# Sheet1.net
KiCad netlist of a schematic drawn in Altium Designer
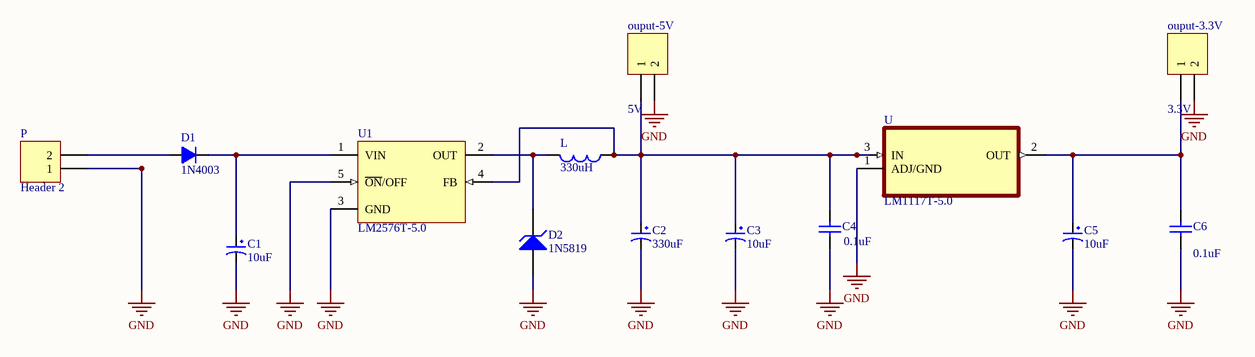
[diagram p0: Sheet1.SchDoc]

(export (version "E")
  (design (tool "Eeschema 10.0.6"))
  (components
    (comp (ref "C1")
      (value "10uF")
      (footprint "CP1/2")
      (description "Cap P  0,1uF < 22uF , 16 - 50V")
      (libsource (lib "syhaunguyen") (part "CP1"))
    )
    (comp (ref "C2")
      (value "330uF")
      (footprint "CP1.5/3.4")
      (description "Cap 100uF/35V - 470uF/16V")
      (libsource (lib "syhaunguyen") (part "CP3"))
    )
    (comp (ref "C3")
      (value "10uF")
      (footprint "CP1/2")
      (description "Cap P  0,1uF < 22uF , 16 - 50V")
      (libsource (lib "syhaunguyen") (part "CP1"))
    )
    (comp (ref "C4")
      (value "0.1uF")
      (footprint "C3MM")
      (description "Capacitor")
      (fields (field (name "PUBLISHER") "Altium Limited"))
      (libsource (lib "Schematic") (part "Cap"))
    )
    (comp (ref "C5")
      (value "10uF")
      (footprint "CP1/2")
      (description "Cap P  0,1uF < 22uF , 16 - 50V")
      (libsource (lib "syhaunguyen") (part "CP1"))
    )
    (comp (ref "C6")
      (value "0.1uF")
      (footprint "C3MM")
      (description "Capacitor")
      (fields (field (name "PUBLISHER") "Altium Limited"))
      (libsource (lib "Schematic") (part "Cap"))
    )
    (comp (ref "D1")
      (value "1N4003")
      (footprint "D1A")
      (description "Diode 1A")
      (libsource (lib "My Library") (part "D1A"))
    )
    (comp (ref "D2")
      (value "1N5819")
      (footprint "DIODE/NOM/0.5A")
      (description "Zener Diode")
      (fields (field (name "PUBLISHER") "Altium Limited"))
      (libsource (lib "My Library") (part "Diode Zener"))
    )
    (comp (ref "L")
      (value "330uH")
      (footprint "L/0.4")
      (description "Inductor")
      (libsource (lib "My Library") (part "L1"))
    )
    (comp (ref "ouput-3.3V")
      (value "3.3V")
      (footprint "HDR1X2")
      (description "Header, 2-Pin")
      (fields (field (name "PUBLISHER") "Altium Limited"))
      (libsource (lib "") (part "Header 2_1"))
    )
    (comp (ref "ouput-5V")
      (value "5V")
      (footprint "HDR1X2")
      (description "Header, 2-Pin")
      (fields (field (name "PUBLISHER") "Altium Limited"))
      (libsource (lib "") (part "Header 2_1"))
    )
    (comp (ref "P")
      (value "Header 2")
      (footprint "HDR1X2")
      (description "Header, 2-Pin")
      (fields (field (name "PUBLISHER") "Altium Limited"))
      (libsource (lib "My Library") (part "Header 2"))
    )
    (comp (ref "U")
      (value "LM1117T-5.0")
      (footprint "TO254P470X1016X2222-3P")
      (description "Linear Voltage Regulator IC 1 Output 800mA TO-220-3")
      (fields (field (name "MF") "Texas Instruments") (field (name "MP") "LM1117T50"))
      (libsource (lib "LM1117T-5.0") (part "LM1117T-5.0"))
    )
    (comp (ref "U1")
      (value "LM2576T-5.0")
      (footprint "LM2576t")
      (description "SIMPLE SWITCHER; 3A Step-Down Voltage Regulator")
      (fields
        (field (name "MANUFACTURER") "National Semiconductor")
        (field (name "DIGIKEYPARTNUMBER") "LM2576T-5.0-ND")
        (field (name "PUBLISHER") "Altium Limited")
      )
      (libsource (lib "My Library") (part "LM2576T-5.0"))
    )
  )
  (nets
    (net (code "1") (name "GND") (class "Default")
      (node (ref "C1") (pin "2") (pinfunction "2_2") (pintype "passive"))
      (node (ref "C2") (pin "2") (pinfunction "2_2") (pintype "passive"))
      (node (ref "C3") (pin "2") (pinfunction "2_2") (pintype "passive"))
      (node (ref "C4") (pin "1") (pinfunction "1_1") (pintype "passive"))
      (node (ref "C5") (pin "2") (pinfunction "2_2") (pintype "passive"))
      (node (ref "C6") (pin "1") (pinfunction "1_1") (pintype "passive"))
      (node (ref "D2") (pin "1") (pinfunction "A_1") (pintype "passive"))
      (node (ref "P") (pin "1") (pinfunction "1_1") (pintype "passive"))
      (node (ref "U") (pin "1") (pinfunction "ADJ/GND_1") (pintype "passive"))
      (node (ref "U1") (pin "3") (pinfunction "GND_3") (pintype "power_in"))
      (node (ref "U1") (pin "5") (pinfunction "~{ON}/OFF_5") (pintype "input"))
      (node (ref "ouput-3.3V") (pin "2") (pinfunction "2_2") (pintype "passive"))
      (node (ref "ouput-5V") (pin "2") (pinfunction "2_2") (pintype "passive"))
    )
    (net (code "2") (name "Net-(D1-A)") (class "Default")
      (node (ref "D1") (pin "1") (pinfunction "A_1") (pintype "passive"))
      (node (ref "P") (pin "2") (pinfunction "2_2") (pintype "passive"))
    )
    (net (code "3") (name "Net-(D1-K)") (class "Default")
      (node (ref "C1") (pin "1") (pinfunction "1_1") (pintype "passive"))
      (node (ref "D1") (pin "2") (pinfunction "K_2") (pintype "passive"))
      (node (ref "U1") (pin "1") (pinfunction "VIN_1") (pintype "power_in"))
    )
    (net (code "4") (name "Net-(D2-K)") (class "Default")
      (node (ref "D2") (pin "2") (pinfunction "K_2") (pintype "passive"))
      (node (ref "L") (pin "2") (pinfunction "2_2") (pintype "passive"))
      (node (ref "U1") (pin "2") (pinfunction "OUT_2") (pintype "power_in"))
    )
    (net (code "5") (name "Net-(U-IN)") (class "Default")
      (node (ref "C2") (pin "1") (pinfunction "1_1") (pintype "passive"))
      (node (ref "C3") (pin "1") (pinfunction "1_1") (pintype "passive"))
      (node (ref "C4") (pin "2") (pinfunction "2_2") (pintype "passive"))
      (node (ref "L") (pin "1") (pinfunction "1_1") (pintype "passive"))
      (node (ref "U") (pin "3") (pinfunction "IN_3") (pintype "input"))
      (node (ref "U1") (pin "4") (pinfunction "FB_4") (pintype "input"))
      (node (ref "ouput-5V") (pin "1") (pinfunction "1_1") (pintype "passive"))
    )
    (net (code "6") (name "Net-(U-OUT)") (class "Default")
      (node (ref "C5") (pin "1") (pinfunction "1_1") (pintype "passive"))
      (node (ref "C6") (pin "2") (pinfunction "2_2") (pintype "passive"))
      (node (ref "U") (pin "2") (pinfunction "OUT_2") (pintype "output"))
      (node (ref "ouput-3.3V") (pin "1") (pinfunction "1_1") (pintype "passive"))
    )
  )
)
